# Launch_Shield.net
KiCad netlist of a schematic drawn in EAGLE
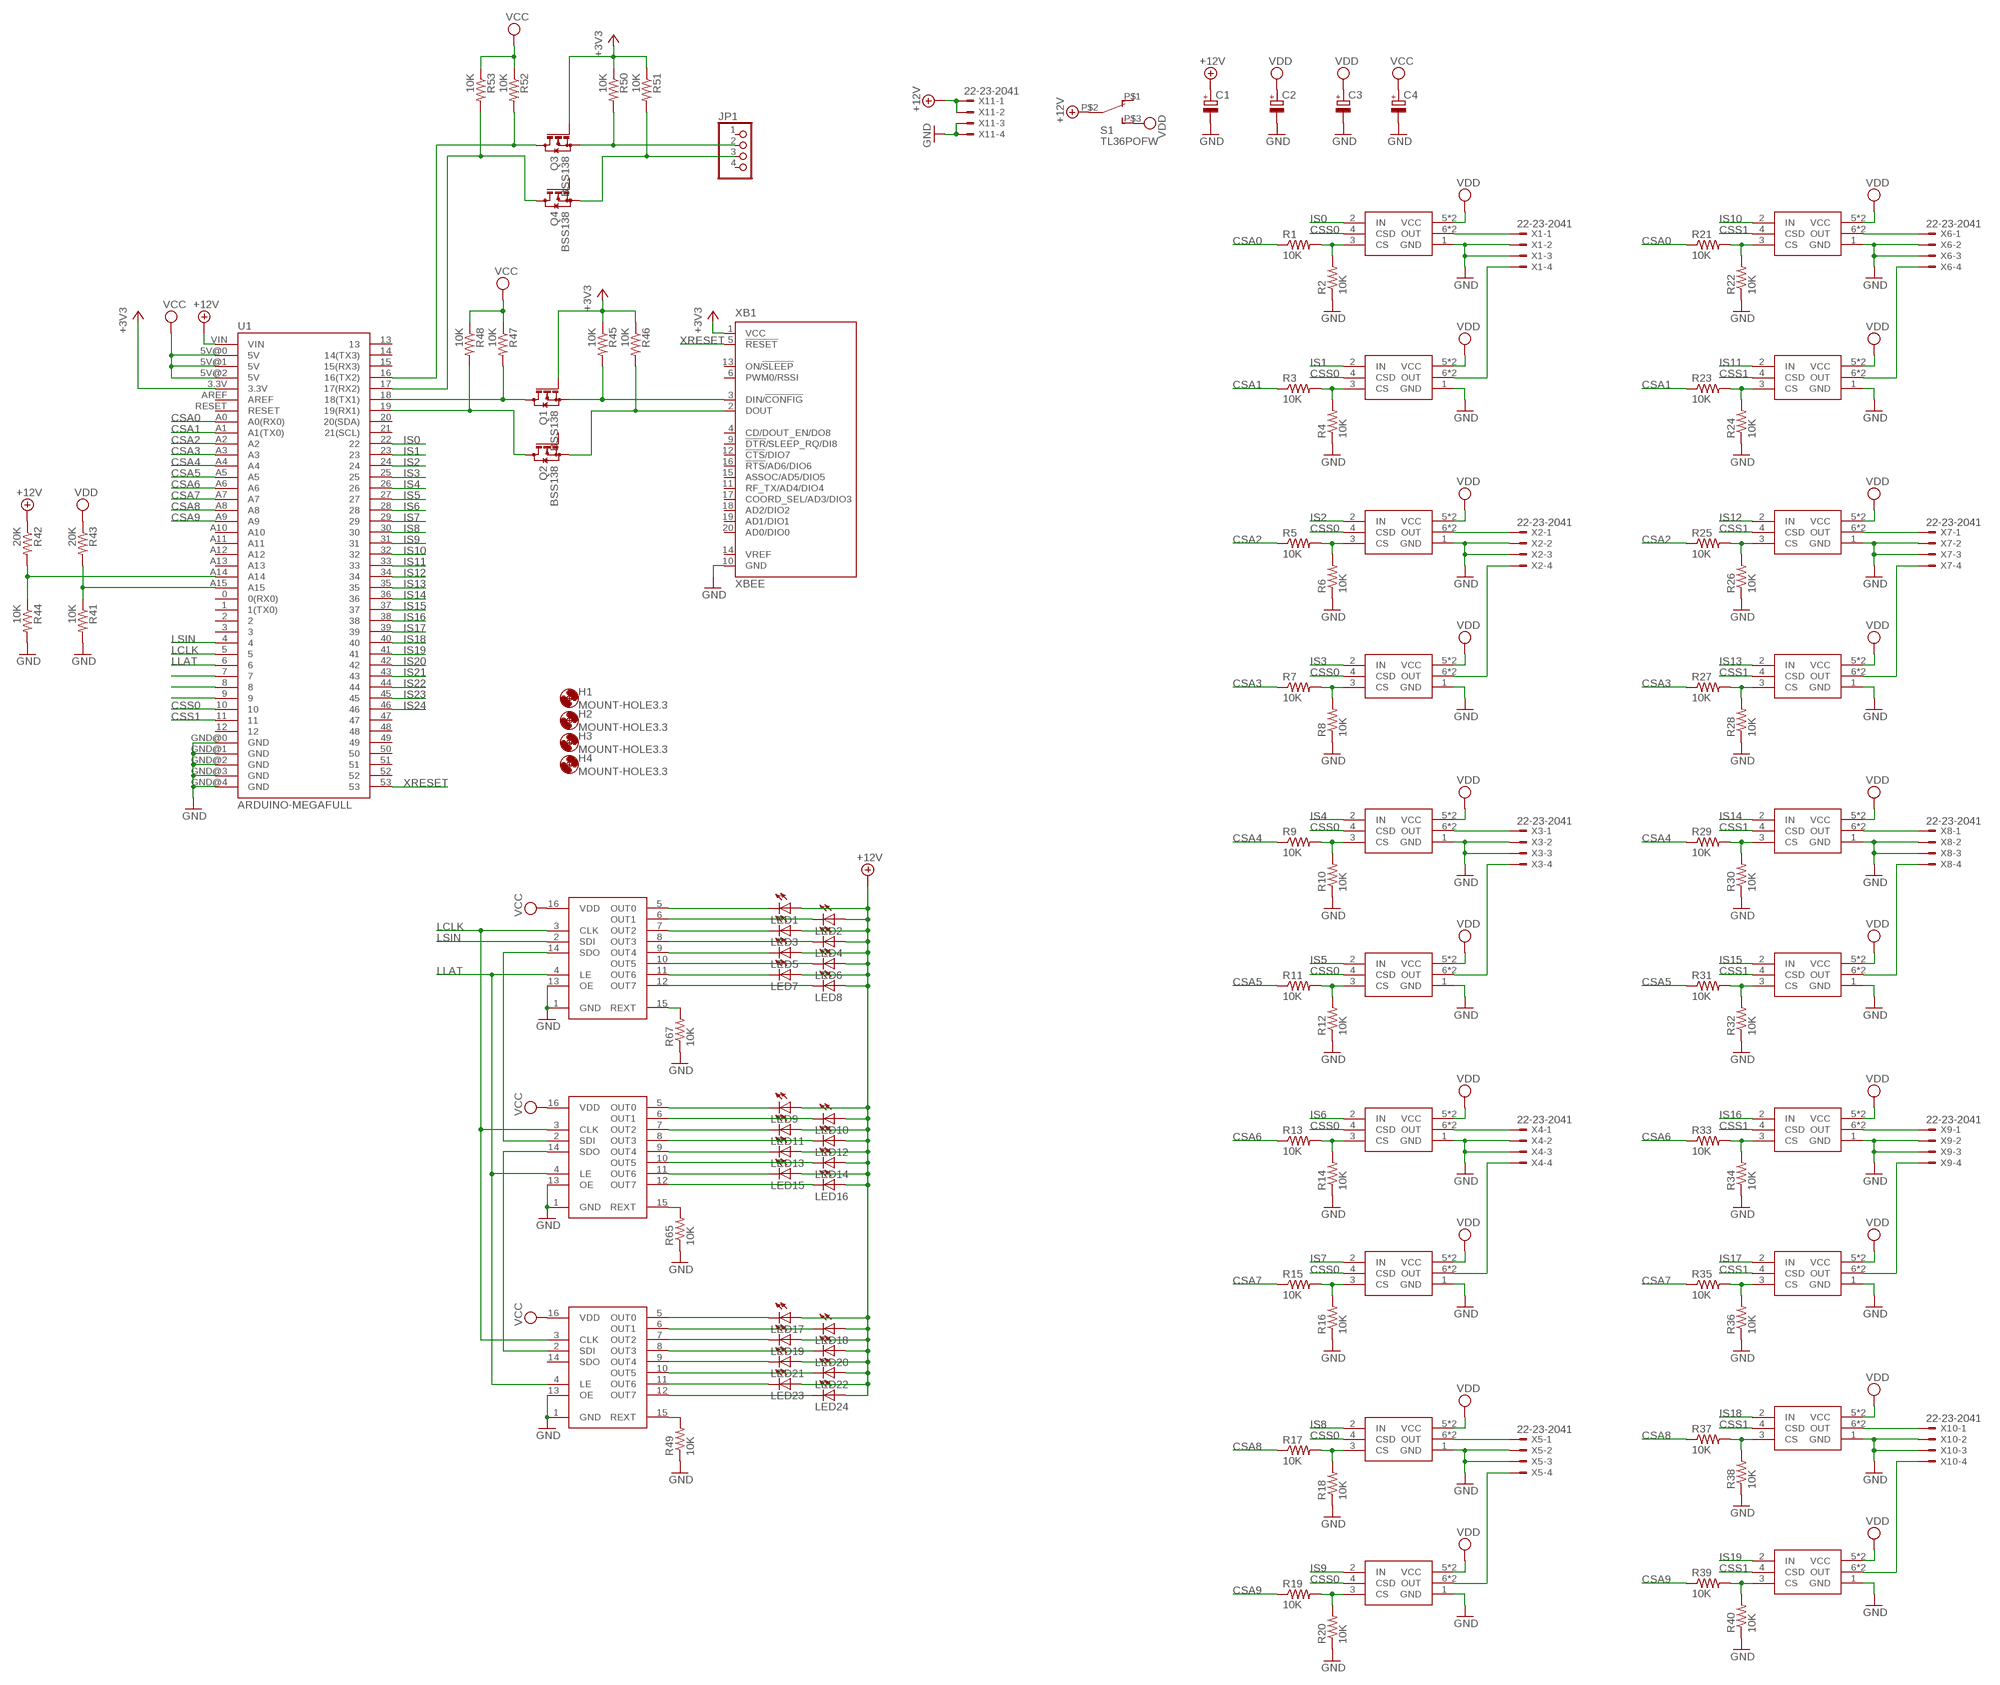
[diagram p0: schematic, sheet 1]

(export (version "E")
  (design (tool "Eeschema 10.0.6"))
  (components
    (comp (ref "C1")
      (value "CPOL-EUE5-6")
      (footprint "eagle-import:E5-6")
      (libsource (lib "eagle-import") (part "CPOL-EUE5-6"))
    )
    (comp (ref "C2")
      (value "CPOL-EUE5-6")
      (footprint "eagle-import:E5-6")
      (libsource (lib "eagle-import") (part "CPOL-EUE5-6"))
    )
    (comp (ref "C3")
      (value "CPOL-EUE5-6")
      (footprint "eagle-import:E5-6")
      (libsource (lib "eagle-import") (part "CPOL-EUE5-6"))
    )
    (comp (ref "C4")
      (value "CPOL-EUE5-6")
      (footprint "eagle-import:E5-6")
      (libsource (lib "eagle-import") (part "CPOL-EUE5-6"))
    )
    (comp (ref "H1")
      (value "MOUNT-HOLE3.3")
      (footprint "eagle-import:3,3")
      (libsource (lib "eagle-import") (part "MOUNT-HOLE3.3"))
    )
    (comp (ref "H2")
      (value "MOUNT-HOLE3.3")
      (footprint "eagle-import:3,3")
      (libsource (lib "eagle-import") (part "MOUNT-HOLE3.3"))
    )
    (comp (ref "H3")
      (value "MOUNT-HOLE3.3")
      (footprint "eagle-import:3,3")
      (libsource (lib "eagle-import") (part "MOUNT-HOLE3.3"))
    )
    (comp (ref "H4")
      (value "MOUNT-HOLE3.3")
      (footprint "eagle-import:3,3")
      (libsource (lib "eagle-import") (part "MOUNT-HOLE3.3"))
    )
    (comp (ref "JP1")
      (value "PINHD-1X4")
      (footprint "eagle-import:1X04")
      (libsource (lib "eagle-import") (part "PINHD-1X4"))
    )
    (comp (ref "LED1")
      (value "LEDCHIPLED_0805")
      (footprint "eagle-import:CHIPLED_0805")
      (libsource (lib "eagle-import") (part "LEDCHIPLED_0805"))
    )
    (comp (ref "LED2")
      (value "LEDCHIPLED_0805")
      (footprint "eagle-import:CHIPLED_0805")
      (libsource (lib "eagle-import") (part "LEDCHIPLED_0805"))
    )
    (comp (ref "LED3")
      (value "LEDCHIPLED_0805")
      (footprint "eagle-import:CHIPLED_0805")
      (libsource (lib "eagle-import") (part "LEDCHIPLED_0805"))
    )
    (comp (ref "LED4")
      (value "LEDCHIPLED_0805")
      (footprint "eagle-import:CHIPLED_0805")
      (libsource (lib "eagle-import") (part "LEDCHIPLED_0805"))
    )
    (comp (ref "LED5")
      (value "LEDCHIPLED_0805")
      (footprint "eagle-import:CHIPLED_0805")
      (libsource (lib "eagle-import") (part "LEDCHIPLED_0805"))
    )
    (comp (ref "LED6")
      (value "LEDCHIPLED_0805")
      (footprint "eagle-import:CHIPLED_0805")
      (libsource (lib "eagle-import") (part "LEDCHIPLED_0805"))
    )
    (comp (ref "LED7")
      (value "LEDCHIPLED_0805")
      (footprint "eagle-import:CHIPLED_0805")
      (libsource (lib "eagle-import") (part "LEDCHIPLED_0805"))
    )
    (comp (ref "LED8")
      (value "LEDCHIPLED_0805")
      (footprint "eagle-import:CHIPLED_0805")
      (libsource (lib "eagle-import") (part "LEDCHIPLED_0805"))
    )
    (comp (ref "LED9")
      (value "LEDCHIPLED_0805")
      (footprint "eagle-import:CHIPLED_0805")
      (libsource (lib "eagle-import") (part "LEDCHIPLED_0805"))
    )
    (comp (ref "LED10")
      (value "LEDCHIPLED_0805")
      (footprint "eagle-import:CHIPLED_0805")
      (libsource (lib "eagle-import") (part "LEDCHIPLED_0805"))
    )
    (comp (ref "LED11")
      (value "LEDCHIPLED_0805")
      (footprint "eagle-import:CHIPLED_0805")
      (libsource (lib "eagle-import") (part "LEDCHIPLED_0805"))
    )
    (comp (ref "LED12")
      (value "LEDCHIPLED_0805")
      (footprint "eagle-import:CHIPLED_0805")
      (libsource (lib "eagle-import") (part "LEDCHIPLED_0805"))
    )
    (comp (ref "LED13")
      (value "LEDCHIPLED_0805")
      (footprint "eagle-import:CHIPLED_0805")
      (libsource (lib "eagle-import") (part "LEDCHIPLED_0805"))
    )
    (comp (ref "LED14")
      (value "LEDCHIPLED_0805")
      (footprint "eagle-import:CHIPLED_0805")
      (libsource (lib "eagle-import") (part "LEDCHIPLED_0805"))
    )
    (comp (ref "LED15")
      (value "LEDCHIPLED_0805")
      (footprint "eagle-import:CHIPLED_0805")
      (libsource (lib "eagle-import") (part "LEDCHIPLED_0805"))
    )
    (comp (ref "LED16")
      (value "LEDCHIPLED_0805")
      (footprint "eagle-import:CHIPLED_0805")
      (libsource (lib "eagle-import") (part "LEDCHIPLED_0805"))
    )
    (comp (ref "LED17")
      (value "LEDCHIPLED_0805")
      (footprint "eagle-import:CHIPLED_0805")
      (libsource (lib "eagle-import") (part "LEDCHIPLED_0805"))
    )
    (comp (ref "LED18")
      (value "LEDCHIPLED_0805")
      (footprint "eagle-import:CHIPLED_0805")
      (libsource (lib "eagle-import") (part "LEDCHIPLED_0805"))
    )
    (comp (ref "LED19")
      (value "LEDCHIPLED_0805")
      (footprint "eagle-import:CHIPLED_0805")
      (libsource (lib "eagle-import") (part "LEDCHIPLED_0805"))
    )
    (comp (ref "LED20")
      (value "LEDCHIPLED_0805")
      (footprint "eagle-import:CHIPLED_0805")
      (libsource (lib "eagle-import") (part "LEDCHIPLED_0805"))
    )
    (comp (ref "LED21")
      (value "LEDCHIPLED_0805")
      (footprint "eagle-import:CHIPLED_0805")
      (libsource (lib "eagle-import") (part "LEDCHIPLED_0805"))
    )
    (comp (ref "LED22")
      (value "LEDCHIPLED_0805")
      (footprint "eagle-import:CHIPLED_0805")
      (libsource (lib "eagle-import") (part "LEDCHIPLED_0805"))
    )
    (comp (ref "LED23")
      (value "LEDCHIPLED_0805")
      (footprint "eagle-import:CHIPLED_0805")
      (libsource (lib "eagle-import") (part "LEDCHIPLED_0805"))
    )
    (comp (ref "LED24")
      (value "LEDCHIPLED_0805")
      (footprint "eagle-import:CHIPLED_0805")
      (libsource (lib "eagle-import") (part "LEDCHIPLED_0805"))
    )
    (comp (ref "Q1")
      (value "BSS138")
      (footprint "eagle-import:SOT23")
      (libsource (lib "eagle-import") (part "BSS123"))
    )
    (comp (ref "Q2")
      (value "BSS138")
      (footprint "eagle-import:SOT23")
      (libsource (lib "eagle-import") (part "BSS123"))
    )
    (comp (ref "Q3")
      (value "BSS138")
      (footprint "eagle-import:SOT23")
      (libsource (lib "eagle-import") (part "BSS123"))
    )
    (comp (ref "Q4")
      (value "BSS138")
      (footprint "eagle-import:SOT23")
      (libsource (lib "eagle-import") (part "BSS123"))
    )
    (comp (ref "R1")
      (value "10K")
      (footprint "eagle-import:R0603")
      (libsource (lib "eagle-import") (part "R-US_R0603"))
    )
    (comp (ref "R2")
      (value "10K")
      (footprint "eagle-import:R0603")
      (libsource (lib "eagle-import") (part "R-US_R0603"))
    )
    (comp (ref "R3")
      (value "10K")
      (footprint "eagle-import:R0603")
      (libsource (lib "eagle-import") (part "R-US_R0603"))
    )
    (comp (ref "R4")
      (value "10K")
      (footprint "eagle-import:R0603")
      (libsource (lib "eagle-import") (part "R-US_R0603"))
    )
    (comp (ref "R5")
      (value "10K")
      (footprint "eagle-import:R0603")
      (libsource (lib "eagle-import") (part "R-US_R0603"))
    )
    (comp (ref "R6")
      (value "10K")
      (footprint "eagle-import:R0603")
      (libsource (lib "eagle-import") (part "R-US_R0603"))
    )
    (comp (ref "R7")
      (value "10K")
      (footprint "eagle-import:R0603")
      (libsource (lib "eagle-import") (part "R-US_R0603"))
    )
    (comp (ref "R8")
      (value "10K")
      (footprint "eagle-import:R0603")
      (libsource (lib "eagle-import") (part "R-US_R0603"))
    )
    (comp (ref "R9")
      (value "10K")
      (footprint "eagle-import:R0603")
      (libsource (lib "eagle-import") (part "R-US_R0603"))
    )
    (comp (ref "R10")
      (value "10K")
      (footprint "eagle-import:R0603")
      (libsource (lib "eagle-import") (part "R-US_R0603"))
    )
    (comp (ref "R11")
      (value "10K")
      (footprint "eagle-import:R0603")
      (libsource (lib "eagle-import") (part "R-US_R0603"))
    )
    (comp (ref "R12")
      (value "10K")
      (footprint "eagle-import:R0603")
      (libsource (lib "eagle-import") (part "R-US_R0603"))
    )
    (comp (ref "R13")
      (value "10K")
      (footprint "eagle-import:R0603")
      (libsource (lib "eagle-import") (part "R-US_R0603"))
    )
    (comp (ref "R14")
      (value "10K")
      (footprint "eagle-import:R0603")
      (libsource (lib "eagle-import") (part "R-US_R0603"))
    )
    (comp (ref "R15")
      (value "10K")
      (footprint "eagle-import:R0603")
      (libsource (lib "eagle-import") (part "R-US_R0603"))
    )
    (comp (ref "R16")
      (value "10K")
      (footprint "eagle-import:R0603")
      (libsource (lib "eagle-import") (part "R-US_R0603"))
    )
    (comp (ref "R17")
      (value "10K")
      (footprint "eagle-import:R0603")
      (libsource (lib "eagle-import") (part "R-US_R0603"))
    )
    (comp (ref "R18")
      (value "10K")
      (footprint "eagle-import:R0603")
      (libsource (lib "eagle-import") (part "R-US_R0603"))
    )
    (comp (ref "R19")
      (value "10K")
      (footprint "eagle-import:R0603")
      (libsource (lib "eagle-import") (part "R-US_R0603"))
    )
    (comp (ref "R20")
      (value "10K")
      (footprint "eagle-import:R0603")
      (libsource (lib "eagle-import") (part "R-US_R0603"))
    )
    (comp (ref "R21")
      (value "10K")
      (footprint "eagle-import:R0603")
      (libsource (lib "eagle-import") (part "R-US_R0603"))
    )
    (comp (ref "R22")
      (value "10K")
      (footprint "eagle-import:R0603")
      (libsource (lib "eagle-import") (part "R-US_R0603"))
    )
    (comp (ref "R23")
      (value "10K")
      (footprint "eagle-import:R0603")
      (libsource (lib "eagle-import") (part "R-US_R0603"))
    )
    (comp (ref "R24")
      (value "10K")
      (footprint "eagle-import:R0603")
      (libsource (lib "eagle-import") (part "R-US_R0603"))
    )
    (comp (ref "R25")
      (value "10K")
      (footprint "eagle-import:R0603")
      (libsource (lib "eagle-import") (part "R-US_R0603"))
    )
    (comp (ref "R26")
      (value "10K")
      (footprint "eagle-import:R0603")
      (libsource (lib "eagle-import") (part "R-US_R0603"))
    )
    (comp (ref "R27")
      (value "10K")
      (footprint "eagle-import:R0603")
      (libsource (lib "eagle-import") (part "R-US_R0603"))
    )
    (comp (ref "R28")
      (value "10K")
      (footprint "eagle-import:R0603")
      (libsource (lib "eagle-import") (part "R-US_R0603"))
    )
    (comp (ref "R29")
      (value "10K")
      (footprint "eagle-import:R0603")
      (libsource (lib "eagle-import") (part "R-US_R0603"))
    )
    (comp (ref "R30")
      (value "10K")
      (footprint "eagle-import:R0603")
      (libsource (lib "eagle-import") (part "R-US_R0603"))
    )
    (comp (ref "R31")
      (value "10K")
      (footprint "eagle-import:R0603")
      (libsource (lib "eagle-import") (part "R-US_R0603"))
    )
    (comp (ref "R32")
      (value "10K")
      (footprint "eagle-import:R0603")
      (libsource (lib "eagle-import") (part "R-US_R0603"))
    )
    (comp (ref "R33")
      (value "10K")
      (footprint "eagle-import:R0603")
      (libsource (lib "eagle-import") (part "R-US_R0603"))
    )
    (comp (ref "R34")
      (value "10K")
      (footprint "eagle-import:R0603")
      (libsource (lib "eagle-import") (part "R-US_R0603"))
    )
    (comp (ref "R35")
      (value "10K")
      (footprint "eagle-import:R0603")
      (libsource (lib "eagle-import") (part "R-US_R0603"))
    )
    (comp (ref "R36")
      (value "10K")
      (footprint "eagle-import:R0603")
      (libsource (lib "eagle-import") (part "R-US_R0603"))
    )
    (comp (ref "R37")
      (value "10K")
      (footprint "eagle-import:R0603")
      (libsource (lib "eagle-import") (part "R-US_R0603"))
    )
    (comp (ref "R38")
      (value "10K")
      (footprint "eagle-import:R0603")
      (libsource (lib "eagle-import") (part "R-US_R0603"))
    )
    (comp (ref "R39")
      (value "10K")
      (footprint "eagle-import:R0603")
      (libsource (lib "eagle-import") (part "R-US_R0603"))
    )
    (comp (ref "R40")
      (value "10K")
      (footprint "eagle-import:R0603")
      (libsource (lib "eagle-import") (part "R-US_R0603"))
    )
    (comp (ref "R41")
      (value "10K")
      (footprint "eagle-import:R0603")
      (libsource (lib "eagle-import") (part "R-US_R0603"))
    )
    (comp (ref "R42")
      (value "20K")
      (footprint "eagle-import:R0603")
      (libsource (lib "eagle-import") (part "R-US_R0603"))
    )
    (comp (ref "R43")
      (value "20K")
      (footprint "eagle-import:R0603")
      (libsource (lib "eagle-import") (part "R-US_R0603"))
    )
    (comp (ref "R44")
      (value "10K")
      (footprint "eagle-import:R0603")
      (libsource (lib "eagle-import") (part "R-US_R0603"))
    )
    (comp (ref "R45")
      (value "10K")
      (footprint "eagle-import:R0603")
      (libsource (lib "eagle-import") (part "R-US_R0603"))
    )
    (comp (ref "R46")
      (value "10K")
      (footprint "eagle-import:R0603")
      (libsource (lib "eagle-import") (part "R-US_R0603"))
    )
    (comp (ref "R47")
      (value "10K")
      (footprint "eagle-import:R0603")
      (libsource (lib "eagle-import") (part "R-US_R0603"))
    )
    (comp (ref "R48")
      (value "10K")
      (footprint "eagle-import:R0603")
      (libsource (lib "eagle-import") (part "R-US_R0603"))
    )
    (comp (ref "R49")
      (value "10K")
      (footprint "eagle-import:R0603")
      (libsource (lib "eagle-import") (part "R-US_R0603"))
    )
    (comp (ref "R50")
      (value "10K")
      (footprint "eagle-import:R0603")
      (libsource (lib "eagle-import") (part "R-US_R0603"))
    )
    (comp (ref "R51")
      (value "10K")
      (footprint "eagle-import:R0603")
      (libsource (lib "eagle-import") (part "R-US_R0603"))
    )
    (comp (ref "R52")
      (value "10K")
      (footprint "eagle-import:R0603")
      (libsource (lib "eagle-import") (part "R-US_R0603"))
    )
    (comp (ref "R53")
      (value "10K")
      (footprint "eagle-import:R0603")
      (libsource (lib "eagle-import") (part "R-US_R0603"))
    )
    (comp (ref "R65")
      (value "10K")
      (footprint "eagle-import:R0603")
      (libsource (lib "eagle-import") (part "R-US_R0603"))
    )
    (comp (ref "R67")
      (value "10K")
      (footprint "eagle-import:R0603")
      (libsource (lib "eagle-import") (part "R-US_R0603"))
    )
    (comp (ref "S1")
      (value "TL36POFW")
      (footprint "eagle-import:TOGGLE")
      (libsource (lib "eagle-import") (part "TL36POFW"))
    )
    (comp (ref "U$1")
      (value "VN5E160MS-E")
      (footprint "eagle-import:SOIC8")
      (libsource (lib "eagle-import") (part "VN5E160MS-E"))
    )
    (comp (ref "U$2")
      (value "VN5E160MS-E")
      (footprint "eagle-import:SOIC8")
      (libsource (lib "eagle-import") (part "VN5E160MS-E"))
    )
    (comp (ref "U$3")
      (value "VN5E160MS-E")
      (footprint "eagle-import:SOIC8")
      (libsource (lib "eagle-import") (part "VN5E160MS-E"))
    )
    (comp (ref "U$4")
      (value "VN5E160MS-E")
      (footprint "eagle-import:SOIC8")
      (libsource (lib "eagle-import") (part "VN5E160MS-E"))
    )
    (comp (ref "U$5")
      (value "VN5E160MS-E")
      (footprint "eagle-import:SOIC8")
      (libsource (lib "eagle-import") (part "VN5E160MS-E"))
    )
    (comp (ref "U$6")
      (value "VN5E160MS-E")
      (footprint "eagle-import:SOIC8")
      (libsource (lib "eagle-import") (part "VN5E160MS-E"))
    )
    (comp (ref "U$7")
      (value "VN5E160MS-E")
      (footprint "eagle-import:SOIC8")
      (libsource (lib "eagle-import") (part "VN5E160MS-E"))
    )
    (comp (ref "U$8")
      (value "VN5E160MS-E")
      (footprint "eagle-import:SOIC8")
      (libsource (lib "eagle-import") (part "VN5E160MS-E"))
    )
    (comp (ref "U$9")
      (value "VN5E160MS-E")
      (footprint "eagle-import:SOIC8")
      (libsource (lib "eagle-import") (part "VN5E160MS-E"))
    )
    (comp (ref "U$10")
      (value "VN5E160MS-E")
      (footprint "eagle-import:SOIC8")
      (libsource (lib "eagle-import") (part "VN5E160MS-E"))
    )
    (comp (ref "U$11")
      (value "VN5E160MS-E")
      (footprint "eagle-import:SOIC8")
      (libsource (lib "eagle-import") (part "VN5E160MS-E"))
    )
    (comp (ref "U$12")
      (value "VN5E160MS-E")
      (footprint "eagle-import:SOIC8")
      (libsource (lib "eagle-import") (part "VN5E160MS-E"))
    )
    (comp (ref "U$13")
      (value "VN5E160MS-E")
      (footprint "eagle-import:SOIC8")
      (libsource (lib "eagle-import") (part "VN5E160MS-E"))
    )
    (comp (ref "U$14")
      (value "VN5E160MS-E")
      (footprint "eagle-import:SOIC8")
      (libsource (lib "eagle-import") (part "VN5E160MS-E"))
    )
    (comp (ref "U$15")
      (value "VN5E160MS-E")
      (footprint "eagle-import:SOIC8")
      (libsource (lib "eagle-import") (part "VN5E160MS-E"))
    )
    (comp (ref "U$16")
      (value "VN5E160MS-E")
      (footprint "eagle-import:SOIC8")
      (libsource (lib "eagle-import") (part "VN5E160MS-E"))
    )
    (comp (ref "U$17")
      (value "VN5E160MS-E")
      (footprint "eagle-import:SOIC8")
      (libsource (lib "eagle-import") (part "VN5E160MS-E"))
    )
    (comp (ref "U$18")
      (value "VN5E160MS-E")
      (footprint "eagle-import:SOIC8")
      (libsource (lib "eagle-import") (part "VN5E160MS-E"))
    )
    (comp (ref "U$19")
      (value "VN5E160MS-E")
      (footprint "eagle-import:SOIC8")
      (libsource (lib "eagle-import") (part "VN5E160MS-E"))
    )
    (comp (ref "U$20")
      (value "VN5E160MS-E")
      (footprint "eagle-import:SOIC8")
      (libsource (lib "eagle-import") (part "VN5E160MS-E"))
    )
    (comp (ref "U$21")
      (value "TLC5916")
      (footprint "eagle-import:D_R-PDSO-G16")
      (libsource (lib "eagle-import") (part "TLC5916"))
    )
    (comp (ref "U$22")
      (value "TLC5916")
      (footprint "eagle-import:D_R-PDSO-G16")
      (libsource (lib "eagle-import") (part "TLC5916"))
    )
    (comp (ref "U$23")
      (value "TLC5916")
      (footprint "eagle-import:D_R-PDSO-G16")
      (libsource (lib "eagle-import") (part "TLC5916"))
    )
    (comp (ref "U1")
      (value "ARDUINO-MEGAFULL")
      (footprint "eagle-import:ARDUINO_MEGA")
      (libsource (lib "eagle-import") (part "ARDUINO-MEGAFULL"))
    )
    (comp (ref "X1")
      (value "22-23-2041")
      (footprint "eagle-import:22-23-2041")
      (fields (field (name "MF") "MOLEX"))
      (libsource (lib "eagle-import") (part "22-23-2041"))
    )
    (comp (ref "X2")
      (value "22-23-2041")
      (footprint "eagle-import:22-23-2041")
      (fields (field (name "MF") "MOLEX"))
      (libsource (lib "eagle-import") (part "22-23-2041"))
    )
    (comp (ref "X3")
      (value "22-23-2041")
      (footprint "eagle-import:22-23-2041")
      (fields (field (name "MF") "MOLEX"))
      (libsource (lib "eagle-import") (part "22-23-2041"))
    )
    (comp (ref "X4")
      (value "22-23-2041")
      (footprint "eagle-import:22-23-2041")
      (fields (field (name "MF") "MOLEX"))
      (libsource (lib "eagle-import") (part "22-23-2041"))
    )
    (comp (ref "X5")
      (value "22-23-2041")
      (footprint "eagle-import:22-23-2041")
      (fields (field (name "MF") "MOLEX"))
      (libsource (lib "eagle-import") (part "22-23-2041"))
    )
    (comp (ref "X6")
      (value "22-23-2041")
      (footprint "eagle-import:22-23-2041")
      (fields (field (name "MF") "MOLEX"))
      (libsource (lib "eagle-import") (part "22-23-2041"))
    )
    (comp (ref "X7")
      (value "22-23-2041")
      (footprint "eagle-import:22-23-2041")
      (fields (field (name "MF") "MOLEX"))
      (libsource (lib "eagle-import") (part "22-23-2041"))
    )
    (comp (ref "X8")
      (value "22-23-2041")
      (footprint "eagle-import:22-23-2041")
      (fields (field (name "MF") "MOLEX"))
      (libsource (lib "eagle-import") (part "22-23-2041"))
    )
    (comp (ref "X9")
      (value "22-23-2041")
      (footprint "eagle-import:22-23-2041")
      (fields (field (name "MF") "MOLEX"))
      (libsource (lib "eagle-import") (part "22-23-2041"))
    )
    (comp (ref "X10")
      (value "22-23-2041")
      (footprint "eagle-import:22-23-2041")
      (fields (field (name "MF") "MOLEX"))
      (libsource (lib "eagle-import") (part "22-23-2041"))
    )
    (comp (ref "X11")
      (value "22-23-2041")
      (footprint "eagle-import:22-23-2041")
      (fields (field (name "MF") "MOLEX"))
      (libsource (lib "eagle-import") (part "22-23-2041"))
    )
    (comp (ref "XB1")
      (value "XBEE")
      (footprint "eagle-import:XBEE")
      (fields (field (name "MPN") "XBP24-Z7UIT-004"))
      (libsource (lib "eagle-import") (part "XBEE"))
    )
  )
  (nets
    (net (code "1") (name "+3V3") (class "Default")
      (node (ref "Q1") (pin "1") (pinfunction "G_1") (pintype "passive"))
      (node (ref "Q3") (pin "1") (pinfunction "G_1") (pintype "passive"))
      (node (ref "R45") (pin "1") (pinfunction "1_1") (pintype "passive"))
      (node (ref "R46") (pin "1") (pinfunction "1_1") (pintype "passive"))
      (node (ref "R50") (pin "1") (pinfunction "1_1") (pintype "passive"))
      (node (ref "R51") (pin "1") (pinfunction "1_1") (pintype "passive"))
      (node (ref "U1") (pin "3.3V") (pinfunction "3.3V_3.3V") (pintype "bidirectional"))
      (node (ref "XB1") (pin "1") (pinfunction "VCC_1") (pintype "power_in"))
    )
    (net (code "2") (name "+12V") (class "Default")
      (node (ref "C1") (pin "+") (pinfunction "+_+") (pintype "passive"))
      (node (ref "LED1") (pin "A") (pinfunction "A_A") (pintype "passive"))
      (node (ref "LED10") (pin "A") (pinfunction "A_A") (pintype "passive"))
      (node (ref "LED11") (pin "A") (pinfunction "A_A") (pintype "passive"))
      (node (ref "LED12") (pin "A") (pinfunction "A_A") (pintype "passive"))
      (node (ref "LED13") (pin "A") (pinfunction "A_A") (pintype "passive"))
      (node (ref "LED14") (pin "A") (pinfunction "A_A") (pintype "passive"))
      (node (ref "LED15") (pin "A") (pinfunction "A_A") (pintype "passive"))
      (node (ref "LED16") (pin "A") (pinfunction "A_A") (pintype "passive"))
      (node (ref "LED17") (pin "A") (pinfunction "A_A") (pintype "passive"))
      (node (ref "LED18") (pin "A") (pinfunction "A_A") (pintype "passive"))
      (node (ref "LED19") (pin "A") (pinfunction "A_A") (pintype "passive"))
      (node (ref "LED2") (pin "A") (pinfunction "A_A") (pintype "passive"))
      (node (ref "LED20") (pin "A") (pinfunction "A_A") (pintype "passive"))
      (node (ref "LED21") (pin "A") (pinfunction "A_A") (pintype "passive"))
      (node (ref "LED22") (pin "A") (pinfunction "A_A") (pintype "passive"))
      (node (ref "LED23") (pin "A") (pinfunction "A_A") (pintype "passive"))
      (node (ref "LED24") (pin "A") (pinfunction "A_A") (pintype "passive"))
      (node (ref "LED3") (pin "A") (pinfunction "A_A") (pintype "passive"))
      (node (ref "LED4") (pin "A") (pinfunction "A_A") (pintype "passive"))
      (node (ref "LED5") (pin "A") (pinfunction "A_A") (pintype "passive"))
      (node (ref "LED6") (pin "A") (pinfunction "A_A") (pintype "passive"))
      (node (ref "LED7") (pin "A") (pinfunction "A_A") (pintype "passive"))
      (node (ref "LED8") (pin "A") (pinfunction "A_A") (pintype "passive"))
      (node (ref "LED9") (pin "A") (pinfunction "A_A") (pintype "passive"))
      (node (ref "R42") (pin "1") (pinfunction "1_1") (pintype "passive"))
      (node (ref "S1") (pin "P$2") (pinfunction "P_P$2") (pintype "passive"))
      (node (ref "U1") (pin "VIN") (pinfunction "VIN_VIN") (pintype "bidirectional"))
      (node (ref "X11") (pin "1") (pinfunction "S_1") (pintype "passive"))
      (node (ref "X11") (pin "2") (pinfunction "S_2") (pintype "passive"))
    )
    (net (code "3") (name "/CSA0") (class "Default")
      (node (ref "R1") (pin "1") (pinfunction "1_1") (pintype "passive"))
      (node (ref "R21") (pin "1") (pinfunction "1_1") (pintype "passive"))
      (node (ref "U1") (pin "A0") (pinfunction "A0(RX0)_A0") (pintype "bidirectional"))
    )
    (net (code "4") (name "/CSA1") (class "Default")
      (node (ref "R23") (pin "1") (pinfunction "1_1") (pintype "passive"))
      (node (ref "R3") (pin "1") (pinfunction "1_1") (pintype "passive"))
      (node (ref "U1") (pin "A1") (pinfunction "A1(TX0)_A1") (pintype "bidirectional"))
    )
    (net (code "5") (name "/CSA2") (class "Default")
      (node (ref "R25") (pin "1") (pinfunction "1_1") (pintype "passive"))
      (node (ref "R5") (pin "1") (pinfunction "1_1") (pintype "passive"))
      (node (ref "U1") (pin "A2") (pinfunction "A2_A2") (pintype "bidirectional"))
    )
    (net (code "6") (name "/CSA3") (class "Default")
      (node (ref "R27") (pin "1") (pinfunction "1_1") (pintype "passive"))
      (node (ref "R7") (pin "1") (pinfunction "1_1") (pintype "passive"))
      (node (ref "U1") (pin "A3") (pinfunction "A3_A3") (pintype "bidirectional"))
    )
    (net (code "7") (name "/CSA4") (class "Default")
      (node (ref "R29") (pin "1") (pinfunction "1_1") (pintype "passive"))
      (node (ref "R9") (pin "1") (pinfunction "1_1") (pintype "passive"))
      (node (ref "U1") (pin "A4") (pinfunction "A4_A4") (pintype "bidirectional"))
    )
    (net (code "8") (name "/CSA5") (class "Default")
      (node (ref "R11") (pin "1") (pinfunction "1_1") (pintype "passive"))
      (node (ref "R31") (pin "1") (pinfunction "1_1") (pintype "passive"))
      (node (ref "U1") (pin "A5") (pinfunction "A5_A5") (pintype "bidirectional"))
    )
    (net (code "9") (name "/CSA6") (class "Default")
      (node (ref "R13") (pin "1") (pinfunction "1_1") (pintype "passive"))
      (node (ref "R33") (pin "1") (pinfunction "1_1") (pintype "passive"))
      (node (ref "U1") (pin "A6") (pinfunction "A6_A6") (pintype "bidirectional"))
    )
    (net (code "10") (name "/CSA7") (class "Default")
      (node (ref "R15") (pin "1") (pinfunction "1_1") (pintype "passive"))
      (node (ref "R35") (pin "1") (pinfunction "1_1") (pintype "passive"))
      (node (ref "U1") (pin "A7") (pinfunction "A7_A7") (pintype "bidirectional"))
    )
    (net (code "11") (name "/CSA8") (class "Default")
      (node (ref "R17") (pin "1") (pinfunction "1_1") (pintype "passive"))
      (node (ref "R37") (pin "1") (pinfunction "1_1") (pintype "passive"))
      (node (ref "U1") (pin "A8") (pinfunction "A8_A8") (pintype "bidirectional"))
    )
    (net (code "12") (name "/CSA9") (class "Default")
      (node (ref "R19") (pin "1") (pinfunction "1_1") (pintype "passive"))
      (node (ref "R39") (pin "1") (pinfunction "1_1") (pintype "passive"))
      (node (ref "U1") (pin "A9") (pinfunction "A9_A9") (pintype "bidirectional"))
    )
    (net (code "13") (name "/CSS0") (class "Default")
      (node (ref "U$1") (pin "4") (pinfunction "CSD_4") (pintype "bidirectional"))
      (node (ref "U$10") (pin "4") (pinfunction "CSD_4") (pintype "bidirectional"))
      (node (ref "U$2") (pin "4") (pinfunction "CSD_4") (pintype "bidirectional"))
      (node (ref "U$3") (pin "4") (pinfunction "CSD_4") (pintype "bidirectional"))
      (node (ref "U$4") (pin "4") (pinfunction "CSD_4") (pintype "bidirectional"))
      (node (ref "U$5") (pin "4") (pinfunction "CSD_4") (pintype "bidirectional"))
      (node (ref "U$6") (pin "4") (pinfunction "CSD_4") (pintype "bidirectional"))
      (node (ref "U$7") (pin "4") (pinfunction "CSD_4") (pintype "bidirectional"))
      (node (ref "U$8") (pin "4") (pinfunction "CSD_4") (pintype "bidirectional"))
      (node (ref "U$9") (pin "4") (pinfunction "CSD_4") (pintype "bidirectional"))
      (node (ref "U1") (pin "10") (pinfunction "10_10") (pintype "bidirectional"))
    )
    (net (code "14") (name "/CSS1") (class "Default")
      (node (ref "U$11") (pin "4") (pinfunction "CSD_4") (pintype "bidirectional"))
      (node (ref "U$12") (pin "4") (pinfunction "CSD_4") (pintype "bidirectional"))
      (node (ref "U$13") (pin "4") (pinfunction "CSD_4") (pintype "bidirectional"))
      (node (ref "U$14") (pin "4") (pinfunction "CSD_4") (pintype "bidirectional"))
      (node (ref "U$15") (pin "4") (pinfunction "CSD_4") (pintype "bidirectional"))
      (node (ref "U$16") (pin "4") (pinfunction "CSD_4") (pintype "bidirectional"))
      (node (ref "U$17") (pin "4") (pinfunction "CSD_4") (pintype "bidirectional"))
      (node (ref "U$18") (pin "4") (pinfunction "CSD_4") (pintype "bidirectional"))
      (node (ref "U$19") (pin "4") (pinfunction "CSD_4") (pintype "bidirectional"))
      (node (ref "U$20") (pin "4") (pinfunction "CSD_4") (pintype "bidirectional"))
      (node (ref "U1") (pin "11") (pinfunction "11_11") (pintype "bidirectional"))
    )
    (net (code "15") (name "/IS0") (class "Default")
      (node (ref "U$1") (pin "2") (pinfunction "IN_2") (pintype "bidirectional"))
      (node (ref "U1") (pin "22") (pinfunction "22_22") (pintype "bidirectional"))
    )
    (net (code "16") (name "/IS1") (class "Default")
      (node (ref "U$2") (pin "2") (pinfunction "IN_2") (pintype "bidirectional"))
      (node (ref "U1") (pin "23") (pinfunction "23_23") (pintype "bidirectional"))
    )
    (net (code "17") (name "/IS2") (class "Default")
      (node (ref "U$3") (pin "2") (pinfunction "IN_2") (pintype "bidirectional"))
      (node (ref "U1") (pin "24") (pinfunction "24_24") (pintype "bidirectional"))
    )
    (net (code "18") (name "/IS3") (class "Default")
      (node (ref "U$4") (pin "2") (pinfunction "IN_2") (pintype "bidirectional"))
      (node (ref "U1") (pin "25") (pinfunction "25_25") (pintype "bidirectional"))
    )
    (net (code "19") (name "/IS4") (class "Default")
      (node (ref "U$5") (pin "2") (pinfunction "IN_2") (pintype "bidirectional"))
      (node (ref "U1") (pin "26") (pinfunction "26_26") (pintype "bidirectional"))
    )
    (net (code "20") (name "/IS5") (class "Default")
      (node (ref "U$6") (pin "2") (pinfunction "IN_2") (pintype "bidirectional"))
      (node (ref "U1") (pin "27") (pinfunction "27_27") (pintype "bidirectional"))
    )
    (net (code "21") (name "/IS6") (class "Default")
      (node (ref "U$7") (pin "2") (pinfunction "IN_2") (pintype "bidirectional"))
      (node (ref "U1") (pin "28") (pinfunction "28_28") (pintype "bidirectional"))
    )
    (net (code "22") (name "/IS7") (class "Default")
      (node (ref "U$8") (pin "2") (pinfunction "IN_2") (pintype "bidirectional"))
      (node (ref "U1") (pin "29") (pinfunction "29_29") (pintype "bidirectional"))
    )
    (net (code "23") (name "/IS8") (class "Default")
      (node (ref "U$9") (pin "2") (pinfunction "IN_2") (pintype "bidirectional"))
      (node (ref "U1") (pin "30") (pinfunction "30_30") (pintype "bidirectional"))
    )
    (net (code "24") (name "/IS9") (class "Default")
      (node (ref "U$10") (pin "2") (pinfunction "IN_2") (pintype "bidirectional"))
      (node (ref "U1") (pin "31") (pinfunction "31_31") (pintype "bidirectional"))
    )
    (net (code "25") (name "/IS10") (class "Default")
      (node (ref "U$11") (pin "2") (pinfunction "IN_2") (pintype "bidirectional"))
      (node (ref "U1") (pin "32") (pinfunction "32_32") (pintype "bidirectional"))
    )
    (net (code "26") (name "/IS11") (class "Default")
      (node (ref "U$12") (pin "2") (pinfunction "IN_2") (pintype "bidirectional"))
      (node (ref "U1") (pin "33") (pinfunction "33_33") (pintype "bidirectional"))
    )
    (net (code "27") (name "/IS12") (class "Default")
      (node (ref "U$13") (pin "2") (pinfunction "IN_2") (pintype "bidirectional"))
      (node (ref "U1") (pin "34") (pinfunction "34_34") (pintype "bidirectional"))
    )
    (net (code "28") (name "/IS13") (class "Default")
      (node (ref "U$14") (pin "2") (pinfunction "IN_2") (pintype "bidirectional"))
      (node (ref "U1") (pin "35") (pinfunction "35_35") (pintype "bidirectional"))
    )
    (net (code "29") (name "/IS14") (class "Default")
      (node (ref "U$15") (pin "2") (pinfunction "IN_2") (pintype "bidirectional"))
      (node (ref "U1") (pin "36") (pinfunction "36_36") (pintype "bidirectional"))
    )
    (net (code "30") (name "/IS15") (class "Default")
      (node (ref "U$16") (pin "2") (pinfunction "IN_2") (pintype "bidirectional"))
      (node (ref "U1") (pin "37") (pinfunction "37_37") (pintype "bidirectional"))
    )
    (net (code "31") (name "/IS16") (class "Default")
      (node (ref "U$17") (pin "2") (pinfunction "IN_2") (pintype "bidirectional"))
      (node (ref "U1") (pin "38") (pinfunction "38_38") (pintype "bidirectional"))
    )
    (net (code "32") (name "/IS17") (class "Default")
      (node (ref "U$18") (pin "2") (pinfunction "IN_2") (pintype "bidirectional"))
      (node (ref "U1") (pin "39") (pinfunction "39_39") (pintype "bidirectional"))
    )
    (net (code "33") (name "/IS18") (class "Default")
      (node (ref "U$19") (pin "2") (pinfunction "IN_2") (pintype "bidirectional"))
      (node (ref "U1") (pin "40") (pinfunction "40_40") (pintype "bidirectional"))
    )
    (net (code "34") (name "/IS19") (class "Default")
      (node (ref "U$20") (pin "2") (pinfunction "IN_2") (pintype "bidirectional"))
      (node (ref "U1") (pin "41") (pinfunction "41_41") (pintype "bidirectional"))
    )
    (net (code "35") (name "/IS20") (class "Default")
      (node (ref "U1") (pin "42") (pinfunction "42_42") (pintype "bidirectional"))
    )
    (net (code "36") (name "/IS21") (class "Default")
      (node (ref "U1") (pin "43") (pinfunction "43_43") (pintype "bidirectional"))
    )
    (net (code "37") (name "/IS22") (class "Default")
      (node (ref "U1") (pin "44") (pinfunction "44_44") (pintype "bidirectional"))
    )
    (net (code "38") (name "/IS23") (class "Default")
      (node (ref "U1") (pin "45") (pinfunction "45_45") (pintype "bidirectional"))
    )
    (net (code "39") (name "/IS24") (class "Default")
      (node (ref "U1") (pin "46") (pinfunction "46_46") (pintype "bidirectional"))
    )
    (net (code "40") (name "/LCLK") (class "Default")
      (node (ref "U$21") (pin "3") (pinfunction "CLK_3") (pintype "bidirectional"))
      (node (ref "U$22") (pin "3") (pinfunction "CLK_3") (pintype "bidirectional"))
      (node (ref "U$23") (pin "3") (pinfunction "CLK_3") (pintype "bidirectional"))
      (node (ref "U1") (pin "5") (pinfunction "5_5") (pintype "bidirectional"))
    )
    (net (code "41") (name "/LLAT") (class "Default")
      (node (ref "U$21") (pin "4") (pinfunction "LE_4") (pintype "bidirectional"))
      (node (ref "U$22") (pin "4") (pinfunction "LE_4") (pintype "bidirectional"))
      (node (ref "U$23") (pin "4") (pinfunction "LE_4") (pintype "bidirectional"))
      (node (ref "U1") (pin "6") (pinfunction "6_6") (pintype "bidirectional"))
    )
    (net (code "42") (name "/LSIN") (class "Default")
      (node (ref "U$21") (pin "2") (pinfunction "SDI_2") (pintype "bidirectional"))
      (node (ref "U1") (pin "4") (pinfunction "4_4") (pintype "bidirectional"))
    )
    (net (code "43") (name "/XRESET") (class "Default")
      (node (ref "U1") (pin "53") (pinfunction "53_53") (pintype "bidirectional"))
      (node (ref "XB1") (pin "5") (pinfunction "~{RESET}_5") (pintype "input"))
    )
    (net (code "44") (name "GND") (class "Default")
      (node (ref "C1") (pin "-") (pinfunction "-_-") (pintype "passive"))
      (node (ref "C2") (pin "-") (pinfunction "-_-") (pintype "passive"))
      (node (ref "C3") (pin "-") (pinfunction "-_-") (pintype "passive"))
      (node (ref "C4") (pin "-") (pinfunction "-_-") (pintype "passive"))
      (node (ref "R10") (pin "1") (pinfunction "1_1") (pintype "passive"))
      (node (ref "R12") (pin "1") (pinfunction "1_1") (pintype "passive"))
      (node (ref "R14") (pin "1") (pinfunction "1_1") (pintype "passive"))
      (node (ref "R16") (pin "1") (pinfunction "1_1") (pintype "passive"))
      (node (ref "R18") (pin "1") (pinfunction "1_1") (pintype "passive"))
      (node (ref "R2") (pin "1") (pinfunction "1_1") (pintype "passive"))
      (node (ref "R20") (pin "1") (pinfunction "1_1") (pintype "passive"))
      (node (ref "R22") (pin "1") (pinfunction "1_1") (pintype "passive"))
      (node (ref "R24") (pin "1") (pinfunction "1_1") (pintype "passive"))
      (node (ref "R26") (pin "1") (pinfunction "1_1") (pintype "passive"))
      (node (ref "R28") (pin "1") (pinfunction "1_1") (pintype "passive"))
      (node (ref "R30") (pin "1") (pinfunction "1_1") (pintype "passive"))
      (node (ref "R32") (pin "1") (pinfunction "1_1") (pintype "passive"))
      (node (ref "R34") (pin "1") (pinfunction "1_1") (pintype "passive"))
      (node (ref "R36") (pin "1") (pinfunction "1_1") (pintype "passive"))
      (node (ref "R38") (pin "1") (pinfunction "1_1") (pintype "passive"))
      (node (ref "R4") (pin "1") (pinfunction "1_1") (pintype "passive"))
      (node (ref "R40") (pin "1") (pinfunction "1_1") (pintype "passive"))
      (node (ref "R41") (pin "2") (pinfunction "2_2") (pintype "passive"))
      (node (ref "R44") (pin "2") (pinfunction "2_2") (pintype "passive"))
      (node (ref "R49") (pin "1") (pinfunction "1_1") (pintype "passive"))
      (node (ref "R6") (pin "1") (pinfunction "1_1") (pintype "passive"))
      (node (ref "R65") (pin "1") (pinfunction "1_1") (pintype "passive"))
      (node (ref "R67") (pin "1") (pinfunction "1_1") (pintype "passive"))
      (node (ref "R8") (pin "1") (pinfunction "1_1") (pintype "passive"))
      (node (ref "U$1") (pin "1") (pinfunction "GND_1") (pintype "power_in"))
      (node (ref "U$10") (pin "1") (pinfunction "GND_1") (pintype "power_in"))
      (node (ref "U$11") (pin "1") (pinfunction "GND_1") (pintype "power_in"))
      (node (ref "U$12") (pin "1") (pinfunction "GND_1") (pintype "power_in"))
      (node (ref "U$13") (pin "1") (pinfunction "GND_1") (pintype "power_in"))
      (node (ref "U$14") (pin "1") (pinfunction "GND_1") (pintype "power_in"))
      (node (ref "U$15") (pin "1") (pinfunction "GND_1") (pintype "power_in"))
      (node (ref "U$16") (pin "1") (pinfunction "GND_1") (pintype "power_in"))
      (node (ref "U$17") (pin "1") (pinfunction "GND_1") (pintype "power_in"))
      (node (ref "U$18") (pin "1") (pinfunction "GND_1") (pintype "power_in"))
      (node (ref "U$19") (pin "1") (pinfunction "GND_1") (pintype "power_in"))
      (node (ref "U$2") (pin "1") (pinfunction "GND_1") (pintype "power_in"))
      (node (ref "U$20") (pin "1") (pinfunction "GND_1") (pintype "power_in"))
      (node (ref "U$21") (pin "1") (pinfunction "GND_1") (pintype "bidirectional"))
      (node (ref "U$21") (pin "13") (pinfunction "OE_13") (pintype "bidirectional"))
      (node (ref "U$22") (pin "1") (pinfunction "GND_1") (pintype "bidirectional"))
      (node (ref "U$22") (pin "13") (pinfunction "OE_13") (pintype "bidirectional"))
      (node (ref "U$23") (pin "1") (pinfunction "GND_1") (pintype "bidirectional"))
      (node (ref "U$23") (pin "13") (pinfunction "OE_13") (pintype "bidirectional"))
      (node (ref "U$3") (pin "1") (pinfunction "GND_1") (pintype "power_in"))
      (node (ref "U$4") (pin "1") (pinfunction "GND_1") (pintype "power_in"))
      (node (ref "U$5") (pin "1") (pinfunction "GND_1") (pintype "power_in"))
      (node (ref "U$6") (pin "1") (pinfunction "GND_1") (pintype "power_in"))
      (node (ref "U$7") (pin "1") (pinfunction "GND_1") (pintype "power_in"))
      (node (ref "U$8") (pin "1") (pinfunction "GND_1") (pintype "power_in"))
      (node (ref "U$9") (pin "1") (pinfunction "GND_1") (pintype "power_in"))
      (node (ref "U1") (pin "GND@0") (pinfunction "GND_GND@0") (pintype "bidirectional"))
      (node (ref "U1") (pin "GND@1") (pinfunction "GND_GND@1") (pintype "bidirectional"))
      (node (ref "U1") (pin "GND@2") (pinfunction "GND_GND@2") (pintype "bidirectional"))
      (node (ref "U1") (pin "GND@3") (pinfunction "GND_GND@3") (pintype "bidirectional"))
      (node (ref "U1") (pin "GND@4") (pinfunction "GND_GND@4") (pintype "bidirectional"))
      (node (ref "X1") (pin "2") (pinfunction "S_2") (pintype "passive"))
      (node (ref "X1") (pin "3") (pinfunction "S_3") (pintype "passive"))
      (node (ref "X10") (pin "2") (pinfunction "S_2") (pintype "passive"))
      (node (ref "X10") (pin "3") (pinfunction "S_3") (pintype "passive"))
      (node (ref "X11") (pin "3") (pinfunction "S_3") (pintype "passive"))
      (node (ref "X11") (pin "4") (pinfunction "S_4") (pintype "passive"))
      (node (ref "X2") (pin "2") (pinfunction "S_2") (pintype "passive"))
      (node (ref "X2") (pin "3") (pinfunction "S_3") (pintype "passive"))
      (node (ref "X3") (pin "2") (pinfunction "S_2") (pintype "passive"))
      (node (ref "X3") (pin "3") (pinfunction "S_3") (pintype "passive"))
      (node (ref "X4") (pin "2") (pinfunction "S_2") (pintype "passive"))
      (node (ref "X4") (pin "3") (pinfunction "S_3") (pintype "passive"))
      (node (ref "X5") (pin "2") (pinfunction "S_2") (pintype "passive"))
      (node (ref "X5") (pin "3") (pinfunction "S_3") (pintype "passive"))
      (node (ref "X6") (pin "2") (pinfunction "S_2") (pintype "passive"))
      (node (ref "X6") (pin "3") (pinfunction "S_3") (pintype "passive"))
      (node (ref "X7") (pin "2") (pinfunction "S_2") (pintype "passive"))
      (node (ref "X7") (pin "3") (pinfunction "S_3") (pintype "passive"))
      (node (ref "X8") (pin "2") (pinfunction "S_2") (pintype "passive"))
      (node (ref "X8") (pin "3") (pinfunction "S_3") (pintype "passive"))
      (node (ref "X9") (pin "2") (pinfunction "S_2") (pintype "passive"))
      (node (ref "X9") (pin "3") (pinfunction "S_3") (pintype "passive"))
      (node (ref "XB1") (pin "10") (pinfunction "GND_10") (pintype "power_in"))
    )
    (net (code "45") (name "Net-(Q1-D)") (class "Default")
      (node (ref "Q1") (pin "3") (pinfunction "D_3") (pintype "passive"))
      (node (ref "R47") (pin "2") (pinfunction "2_2") (pintype "passive"))
      (node (ref "U1") (pin "18") (pinfunction "18(TX1)_18") (pintype "bidirectional"))
    )
    (net (code "46") (name "Net-(Q1-S)") (class "Default")
      (node (ref "Q1") (pin "2") (pinfunction "S_2") (pintype "passive"))
      (node (ref "R45") (pin "2") (pinfunction "2_2") (pintype "passive"))
      (node (ref "XB1") (pin "3") (pinfunction "DIN/~{CONFIG}_3") (pintype "input"))
    )
    (net (code "47") (name "Net-(Q2-D)") (class "Default")
      (node (ref "Q2") (pin "3") (pinfunction "D_3") (pintype "passive"))
      (node (ref "R48") (pin "2") (pinfunction "2_2") (pintype "passive"))
      (node (ref "U1") (pin "19") (pinfunction "19(RX1)_19") (pintype "bidirectional"))
    )
    (net (code "48") (name "Net-(Q2-S)") (class "Default")
      (node (ref "Q2") (pin "2") (pinfunction "S_2") (pintype "passive"))
      (node (ref "R46") (pin "2") (pinfunction "2_2") (pintype "passive"))
      (node (ref "XB1") (pin "2") (pinfunction "DOUT_2") (pintype "output"))
    )
    (net (code "49") (name "Net-(Q3-D)") (class "Default")
      (node (ref "Q3") (pin "3") (pinfunction "D_3") (pintype "passive"))
      (node (ref "R52") (pin "2") (pinfunction "2_2") (pintype "passive"))
      (node (ref "U1") (pin "16") (pinfunction "16(TX2)_16") (pintype "bidirectional"))
    )
    (net (code "50") (name "Net-(Q3-S)") (class "Default")
      (node (ref "JP1") (pin "2") (pinfunction "2_2") (pintype "passive"))
      (node (ref "Q3") (pin "2") (pinfunction "S_2") (pintype "passive"))
      (node (ref "R50") (pin "2") (pinfunction "2_2") (pintype "passive"))
    )
    (net (code "51") (name "Net-(Q4-D)") (class "Default")
      (node (ref "Q4") (pin "3") (pinfunction "D_3") (pintype "passive"))
      (node (ref "R53") (pin "2") (pinfunction "2_2") (pintype "passive"))
      (node (ref "U1") (pin "17") (pinfunction "17(RX2)_17") (pintype "bidirectional"))
    )
    (net (code "52") (name "Net-(Q4-S)") (class "Default")
      (node (ref "JP1") (pin "3") (pinfunction "3_3") (pintype "passive"))
      (node (ref "Q4") (pin "2") (pinfunction "S_2") (pintype "passive"))
      (node (ref "R51") (pin "2") (pinfunction "2_2") (pintype "passive"))
    )
    (net (code "53") (name "Net-(R41-Pad1)") (class "Default")
      (node (ref "R41") (pin "1") (pinfunction "1_1") (pintype "passive"))
      (node (ref "R43") (pin "2") (pinfunction "2_2") (pintype "passive"))
      (node (ref "U1") (pin "A15") (pinfunction "A15_A15") (pintype "bidirectional"))
    )
    (net (code "54") (name "Net-(R42-Pad2)") (class "Default")
      (node (ref "R42") (pin "2") (pinfunction "2_2") (pintype "passive"))
      (node (ref "R44") (pin "1") (pinfunction "1_1") (pintype "passive"))
      (node (ref "U1") (pin "A14") (pinfunction "A14_A14") (pintype "bidirectional"))
    )
    (net (code "55") (name "Net-(U$1-CS)") (class "Default")
      (node (ref "R1") (pin "2") (pinfunction "2_2") (pintype "passive"))
      (node (ref "R2") (pin "2") (pinfunction "2_2") (pintype "passive"))
      (node (ref "U$1") (pin "3") (pinfunction "CS_3") (pintype "bidirectional"))
    )
    (net (code "56") (name "Net-(U$2-CS)") (class "Default")
      (node (ref "R3") (pin "2") (pinfunction "2_2") (pintype "passive"))
      (node (ref "R4") (pin "2") (pinfunction "2_2") (pintype "passive"))
      (node (ref "U$2") (pin "3") (pinfunction "CS_3") (pintype "bidirectional"))
    )
    (net (code "57") (name "Net-(U$3-CS)") (class "Default")
      (node (ref "R5") (pin "2") (pinfunction "2_2") (pintype "passive"))
      (node (ref "R6") (pin "2") (pinfunction "2_2") (pintype "passive"))
      (node (ref "U$3") (pin "3") (pinfunction "CS_3") (pintype "bidirectional"))
    )
    (net (code "58") (name "Net-(U$4-CS)") (class "Default")
      (node (ref "R7") (pin "2") (pinfunction "2_2") (pintype "passive"))
      (node (ref "R8") (pin "2") (pinfunction "2_2") (pintype "passive"))
      (node (ref "U$4") (pin "3") (pinfunction "CS_3") (pintype "bidirectional"))
    )
    (net (code "59") (name "Net-(U$5-CS)") (class "Default")
      (node (ref "R10") (pin "2") (pinfunction "2_2") (pintype "passive"))
      (node (ref "R9") (pin "2") (pinfunction "2_2") (pintype "passive"))
      (node (ref "U$5") (pin "3") (pinfunction "CS_3") (pintype "bidirectional"))
    )
    (net (code "60") (name "Net-(U$6-CS)") (class "Default")
      (node (ref "R11") (pin "2") (pinfunction "2_2") (pintype "passive"))
      (node (ref "R12") (pin "2") (pinfunction "2_2") (pintype "passive"))
      (node (ref "U$6") (pin "3") (pinfunction "CS_3") (pintype "bidirectional"))
    )
    (net (code "61") (name "Net-(U$7-CS)") (class "Default")
      (node (ref "R13") (pin "2") (pinfunction "2_2") (pintype "passive"))
      (node (ref "R14") (pin "2") (pinfunction "2_2") (pintype "passive"))
      (node (ref "U$7") (pin "3") (pinfunction "CS_3") (pintype "bidirectional"))
    )
    (net (code "62") (name "Net-(U$8-CS)") (class "Default")
      (node (ref "R15") (pin "2") (pinfunction "2_2") (pintype "passive"))
      (node (ref "R16") (pin "2") (pinfunction "2_2") (pintype "passive"))
      (node (ref "U$8") (pin "3") (pinfunction "CS_3") (pintype "bidirectional"))
    )
    (net (code "63") (name "Net-(U$9-CS)") (class "Default")
      (node (ref "R17") (pin "2") (pinfunction "2_2") (pintype "passive"))
      (node (ref "R18") (pin "2") (pinfunction "2_2") (pintype "passive"))
      (node (ref "U$9") (pin "3") (pinfunction "CS_3") (pintype "bidirectional"))
    )
    (net (code "64") (name "Net-(U$10-CS)") (class "Default")
      (node (ref "R19") (pin "2") (pinfunction "2_2") (pintype "passive"))
      (node (ref "R20") (pin "2") (pinfunction "2_2") (pintype "passive"))
      (node (ref "U$10") (pin "3") (pinfunction "CS_3") (pintype "bidirectional"))
    )
    (net (code "65") (name "Net-(U$11-CS)") (class "Default")
      (node (ref "R21") (pin "2") (pinfunction "2_2") (pintype "passive"))
      (node (ref "R22") (pin "2") (pinfunction "2_2") (pintype "passive"))
      (node (ref "U$11") (pin "3") (pinfunction "CS_3") (pintype "bidirectional"))
    )
    (net (code "66") (name "Net-(U$12-CS)") (class "Default")
      (node (ref "R23") (pin "2") (pinfunction "2_2") (pintype "passive"))
      (node (ref "R24") (pin "2") (pinfunction "2_2") (pintype "passive"))
      (node (ref "U$12") (pin "3") (pinfunction "CS_3") (pintype "bidirectional"))
    )
    (net (code "67") (name "Net-(U$13-CS)") (class "Default")
      (node (ref "R25") (pin "2") (pinfunction "2_2") (pintype "passive"))
      (node (ref "R26") (pin "2") (pinfunction "2_2") (pintype "passive"))
      (node (ref "U$13") (pin "3") (pinfunction "CS_3") (pintype "bidirectional"))
    )
    (net (code "68") (name "Net-(U$14-CS)") (class "Default")
      (node (ref "R27") (pin "2") (pinfunction "2_2") (pintype "passive"))
      (node (ref "R28") (pin "2") (pinfunction "2_2") (pintype "passive"))
      (node (ref "U$14") (pin "3") (pinfunction "CS_3") (pintype "bidirectional"))
    )
    (net (code "69") (name "Net-(U$15-CS)") (class "Default")
      (node (ref "R29") (pin "2") (pinfunction "2_2") (pintype "passive"))
      (node (ref "R30") (pin "2") (pinfunction "2_2") (pintype "passive"))
      (node (ref "U$15") (pin "3") (pinfunction "CS_3") (pintype "bidirectional"))
    )
    (net (code "70") (name "Net-(U$16-CS)") (class "Default")
      (node (ref "R31") (pin "2") (pinfunction "2_2") (pintype "passive"))
      (node (ref "R32") (pin "2") (pinfunction "2_2") (pintype "passive"))
      (node (ref "U$16") (pin "3") (pinfunction "CS_3") (pintype "bidirectional"))
    )
    (net (code "71") (name "Net-(U$17-CS)") (class "Default")
      (node (ref "R33") (pin "2") (pinfunction "2_2") (pintype "passive"))
      (node (ref "R34") (pin "2") (pinfunction "2_2") (pintype "passive"))
      (node (ref "U$17") (pin "3") (pinfunction "CS_3") (pintype "bidirectional"))
    )
    (net (code "72") (name "Net-(U$18-CS)") (class "Default")
      (node (ref "R35") (pin "2") (pinfunction "2_2") (pintype "passive"))
      (node (ref "R36") (pin "2") (pinfunction "2_2") (pintype "passive"))
      (node (ref "U$18") (pin "3") (pinfunction "CS_3") (pintype "bidirectional"))
    )
    (net (code "73") (name "Net-(U$19-CS)") (class "Default")
      (node (ref "R37") (pin "2") (pinfunction "2_2") (pintype "passive"))
      (node (ref "R38") (pin "2") (pinfunction "2_2") (pintype "passive"))
      (node (ref "U$19") (pin "3") (pinfunction "CS_3") (pintype "bidirectional"))
    )
    (net (code "74") (name "Net-(U$20-CS)") (class "Default")
      (node (ref "R39") (pin "2") (pinfunction "2_2") (pintype "passive"))
      (node (ref "R40") (pin "2") (pinfunction "2_2") (pintype "passive"))
      (node (ref "U$20") (pin "3") (pinfunction "CS_3") (pintype "bidirectional"))
    )
    (net (code "75") (name "Net-(U$21-OUT0)") (class "Default")
      (node (ref "LED1") (pin "C") (pinfunction "C_C") (pintype "passive"))
      (node (ref "U$21") (pin "5") (pinfunction "OUT0_5") (pintype "bidirectional"))
    )
    (net (code "76") (name "Net-(U$21-OUT1)") (class "Default")
      (node (ref "LED2") (pin "C") (pinfunction "C_C") (pintype "passive"))
      (node (ref "U$21") (pin "6") (pinfunction "OUT1_6") (pintype "bidirectional"))
    )
    (net (code "77") (name "Net-(U$21-OUT2)") (class "Default")
      (node (ref "LED3") (pin "C") (pinfunction "C_C") (pintype "passive"))
      (node (ref "U$21") (pin "7") (pinfunction "OUT2_7") (pintype "bidirectional"))
    )
    (net (code "78") (name "Net-(U$21-OUT3)") (class "Default")
      (node (ref "LED4") (pin "C") (pinfunction "C_C") (pintype "passive"))
      (node (ref "U$21") (pin "8") (pinfunction "OUT3_8") (pintype "bidirectional"))
    )
    (net (code "79") (name "Net-(U$21-OUT4)") (class "Default")
      (node (ref "LED5") (pin "C") (pinfunction "C_C") (pintype "passive"))
      (node (ref "U$21") (pin "9") (pinfunction "OUT4_9") (pintype "bidirectional"))
    )
    (net (code "80") (name "Net-(U$21-OUT5)") (class "Default")
      (node (ref "LED6") (pin "C") (pinfunction "C_C") (pintype "passive"))
      (node (ref "U$21") (pin "10") (pinfunction "OUT5_10") (pintype "bidirectional"))
    )
    (net (code "81") (name "Net-(U$21-OUT6)") (class "Default")
      (node (ref "LED7") (pin "C") (pinfunction "C_C") (pintype "passive"))
      (node (ref "U$21") (pin "11") (pinfunction "OUT6_11") (pintype "bidirectional"))
    )
    (net (code "82") (name "Net-(U$21-OUT7)") (class "Default")
      (node (ref "LED8") (pin "C") (pinfunction "C_C") (pintype "passive"))
      (node (ref "U$21") (pin "12") (pinfunction "OUT7_12") (pintype "bidirectional"))
    )
    (net (code "83") (name "Net-(U$21-REXT)") (class "Default")
      (node (ref "R67") (pin "2") (pinfunction "2_2") (pintype "passive"))
      (node (ref "U$21") (pin "15") (pinfunction "REXT_15") (pintype "bidirectional"))
    )
    (net (code "84") (name "Net-(U$21-SDO)") (class "Default")
      (node (ref "U$21") (pin "14") (pinfunction "SDO_14") (pintype "bidirectional"))
      (node (ref "U$22") (pin "2") (pinfunction "SDI_2") (pintype "bidirectional"))
    )
    (net (code "85") (name "Net-(U$22-OUT0)") (class "Default")
      (node (ref "LED9") (pin "C") (pinfunction "C_C") (pintype "passive"))
      (node (ref "U$22") (pin "5") (pinfunction "OUT0_5") (pintype "bidirectional"))
    )
    (net (code "86") (name "Net-(U$22-OUT1)") (class "Default")
      (node (ref "LED10") (pin "C") (pinfunction "C_C") (pintype "passive"))
      (node (ref "U$22") (pin "6") (pinfunction "OUT1_6") (pintype "bidirectional"))
    )
    (net (code "87") (name "Net-(U$22-OUT2)") (class "Default")
      (node (ref "LED11") (pin "C") (pinfunction "C_C") (pintype "passive"))
      (node (ref "U$22") (pin "7") (pinfunction "OUT2_7") (pintype "bidirectional"))
    )
    (net (code "88") (name "Net-(U$22-OUT3)") (class "Default")
      (node (ref "LED12") (pin "C") (pinfunction "C_C") (pintype "passive"))
      (node (ref "U$22") (pin "8") (pinfunction "OUT3_8") (pintype "bidirectional"))
    )
    (net (code "89") (name "Net-(U$22-OUT4)") (class "Default")
      (node (ref "LED13") (pin "C") (pinfunction "C_C") (pintype "passive"))
      (node (ref "U$22") (pin "9") (pinfunction "OUT4_9") (pintype "bidirectional"))
    )
    (net (code "90") (name "Net-(U$22-OUT5)") (class "Default")
      (node (ref "LED14") (pin "C") (pinfunction "C_C") (pintype "passive"))
      (node (ref "U$22") (pin "10") (pinfunction "OUT5_10") (pintype "bidirectional"))
    )
    (net (code "91") (name "Net-(U$22-OUT6)") (class "Default")
      (node (ref "LED15") (pin "C") (pinfunction "C_C") (pintype "passive"))
      (node (ref "U$22") (pin "11") (pinfunction "OUT6_11") (pintype "bidirectional"))
    )
    (net (code "92") (name "Net-(U$22-OUT7)") (class "Default")
      (node (ref "LED16") (pin "C") (pinfunction "C_C") (pintype "passive"))
      (node (ref "U$22") (pin "12") (pinfunction "OUT7_12") (pintype "bidirectional"))
    )
    (net (code "93") (name "Net-(U$22-REXT)") (class "Default")
      (node (ref "R65") (pin "2") (pinfunction "2_2") (pintype "passive"))
      (node (ref "U$22") (pin "15") (pinfunction "REXT_15") (pintype "bidirectional"))
    )
    (net (code "94") (name "Net-(U$22-SDO)") (class "Default")
      (node (ref "U$22") (pin "14") (pinfunction "SDO_14") (pintype "bidirectional"))
      (node (ref "U$23") (pin "2") (pinfunction "SDI_2") (pintype "bidirectional"))
    )
    (net (code "95") (name "Net-(U$23-OUT0)") (class "Default")
      (node (ref "LED17") (pin "C") (pinfunction "C_C") (pintype "passive"))
      (node (ref "U$23") (pin "5") (pinfunction "OUT0_5") (pintype "bidirectional"))
    )
    (net (code "96") (name "Net-(U$23-OUT1)") (class "Default")
      (node (ref "LED18") (pin "C") (pinfunction "C_C") (pintype "passive"))
      (node (ref "U$23") (pin "6") (pinfunction "OUT1_6") (pintype "bidirectional"))
    )
    (net (code "97") (name "Net-(U$23-OUT2)") (class "Default")
      (node (ref "LED19") (pin "C") (pinfunction "C_C") (pintype "passive"))
      (node (ref "U$23") (pin "7") (pinfunction "OUT2_7") (pintype "bidirectional"))
    )
    (net (code "98") (name "Net-(U$23-OUT3)") (class "Default")
      (node (ref "LED20") (pin "C") (pinfunction "C_C") (pintype "passive"))
      (node (ref "U$23") (pin "8") (pinfunction "OUT3_8") (pintype "bidirectional"))
    )
    (net (code "99") (name "Net-(U$23-OUT4)") (class "Default")
      (node (ref "LED21") (pin "C") (pinfunction "C_C") (pintype "passive"))
      (node (ref "U$23") (pin "9") (pinfunction "OUT4_9") (pintype "bidirectional"))
    )
    (net (code "100") (name "Net-(U$23-OUT5)") (class "Default")
      (node (ref "LED22") (pin "C") (pinfunction "C_C") (pintype "passive"))
      (node (ref "U$23") (pin "10") (pinfunction "OUT5_10") (pintype "bidirectional"))
    )
    (net (code "101") (name "Net-(U$23-OUT6)") (class "Default")
      (node (ref "LED23") (pin "C") (pinfunction "C_C") (pintype "passive"))
      (node (ref "U$23") (pin "11") (pinfunction "OUT6_11") (pintype "bidirectional"))
    )
    (net (code "102") (name "Net-(U$23-OUT7)") (class "Default")
      (node (ref "LED24") (pin "C") (pinfunction "C_C") (pintype "passive"))
      (node (ref "U$23") (pin "12") (pinfunction "OUT7_12") (pintype "bidirectional"))
    )
    (net (code "103") (name "Net-(U$23-REXT)") (class "Default")
      (node (ref "R49") (pin "2") (pinfunction "2_2") (pintype "passive"))
      (node (ref "U$23") (pin "15") (pinfunction "REXT_15") (pintype "bidirectional"))
    )
    (net (code "104") (name "Net-(X1A-S)") (class "Default")
      (node (ref "U$1") (pin "6") (pinfunction "OUT_6") (pintype "output"))
      (node (ref "U$1") (pin "7") (pinfunction "OUT_7") (pintype "output"))
      (node (ref "X1") (pin "1") (pinfunction "S_1") (pintype "passive"))
    )
    (net (code "105") (name "Net-(X1D-S)") (class "Default")
      (node (ref "U$2") (pin "6") (pinfunction "OUT_6") (pintype "output"))
      (node (ref "U$2") (pin "7") (pinfunction "OUT_7") (pintype "output"))
      (node (ref "X1") (pin "4") (pinfunction "S_4") (pintype "passive"))
    )
    (net (code "106") (name "Net-(X2A-S)") (class "Default")
      (node (ref "U$3") (pin "6") (pinfunction "OUT_6") (pintype "output"))
      (node (ref "U$3") (pin "7") (pinfunction "OUT_7") (pintype "output"))
      (node (ref "X2") (pin "1") (pinfunction "S_1") (pintype "passive"))
    )
    (net (code "107") (name "Net-(X2D-S)") (class "Default")
      (node (ref "U$4") (pin "6") (pinfunction "OUT_6") (pintype "output"))
      (node (ref "U$4") (pin "7") (pinfunction "OUT_7") (pintype "output"))
      (node (ref "X2") (pin "4") (pinfunction "S_4") (pintype "passive"))
    )
    (net (code "108") (name "Net-(X3A-S)") (class "Default")
      (node (ref "U$5") (pin "6") (pinfunction "OUT_6") (pintype "output"))
      (node (ref "U$5") (pin "7") (pinfunction "OUT_7") (pintype "output"))
      (node (ref "X3") (pin "1") (pinfunction "S_1") (pintype "passive"))
    )
    (net (code "109") (name "Net-(X3D-S)") (class "Default")
      (node (ref "U$6") (pin "6") (pinfunction "OUT_6") (pintype "output"))
      (node (ref "U$6") (pin "7") (pinfunction "OUT_7") (pintype "output"))
      (node (ref "X3") (pin "4") (pinfunction "S_4") (pintype "passive"))
    )
    (net (code "110") (name "Net-(X4A-S)") (class "Default")
      (node (ref "U$7") (pin "6") (pinfunction "OUT_6") (pintype "output"))
      (node (ref "U$7") (pin "7") (pinfunction "OUT_7") (pintype "output"))
      (node (ref "X4") (pin "1") (pinfunction "S_1") (pintype "passive"))
    )
    (net (code "111") (name "Net-(X4D-S)") (class "Default")
      (node (ref "U$8") (pin "6") (pinfunction "OUT_6") (pintype "output"))
      (node (ref "U$8") (pin "7") (pinfunction "OUT_7") (pintype "output"))
      (node (ref "X4") (pin "4") (pinfunction "S_4") (pintype "passive"))
    )
    (net (code "112") (name "Net-(X5A-S)") (class "Default")
      (node (ref "U$9") (pin "6") (pinfunction "OUT_6") (pintype "output"))
      (node (ref "U$9") (pin "7") (pinfunction "OUT_7") (pintype "output"))
      (node (ref "X5") (pin "1") (pinfunction "S_1") (pintype "passive"))
    )
    (net (code "113") (name "Net-(X5D-S)") (class "Default")
      (node (ref "U$10") (pin "6") (pinfunction "OUT_6") (pintype "output"))
      (node (ref "U$10") (pin "7") (pinfunction "OUT_7") (pintype "output"))
      (node (ref "X5") (pin "4") (pinfunction "S_4") (pintype "passive"))
    )
    (net (code "114") (name "Net-(X6A-S)") (class "Default")
      (node (ref "U$11") (pin "6") (pinfunction "OUT_6") (pintype "output"))
      (node (ref "U$11") (pin "7") (pinfunction "OUT_7") (pintype "output"))
      (node (ref "X6") (pin "1") (pinfunction "S_1") (pintype "passive"))
    )
    (net (code "115") (name "Net-(X6D-S)") (class "Default")
      (node (ref "U$12") (pin "6") (pinfunction "OUT_6") (pintype "output"))
      (node (ref "U$12") (pin "7") (pinfunction "OUT_7") (pintype "output"))
      (node (ref "X6") (pin "4") (pinfunction "S_4") (pintype "passive"))
    )
    (net (code "116") (name "Net-(X7A-S)") (class "Default")
      (node (ref "U$13") (pin "6") (pinfunction "OUT_6") (pintype "output"))
      (node (ref "U$13") (pin "7") (pinfunction "OUT_7") (pintype "output"))
      (node (ref "X7") (pin "1") (pinfunction "S_1") (pintype "passive"))
    )
    (net (code "117") (name "Net-(X7D-S)") (class "Default")
      (node (ref "U$14") (pin "6") (pinfunction "OUT_6") (pintype "output"))
      (node (ref "U$14") (pin "7") (pinfunction "OUT_7") (pintype "output"))
      (node (ref "X7") (pin "4") (pinfunction "S_4") (pintype "passive"))
    )
    (net (code "118") (name "Net-(X8A-S)") (class "Default")
      (node (ref "U$15") (pin "6") (pinfunction "OUT_6") (pintype "output"))
      (node (ref "U$15") (pin "7") (pinfunction "OUT_7") (pintype "output"))
      (node (ref "X8") (pin "1") (pinfunction "S_1") (pintype "passive"))
    )
    (net (code "119") (name "Net-(X8D-S)") (class "Default")
      (node (ref "U$16") (pin "6") (pinfunction "OUT_6") (pintype "output"))
      (node (ref "U$16") (pin "7") (pinfunction "OUT_7") (pintype "output"))
      (node (ref "X8") (pin "4") (pinfunction "S_4") (pintype "passive"))
    )
    (net (code "120") (name "Net-(X9A-S)") (class "Default")
      (node (ref "U$17") (pin "6") (pinfunction "OUT_6") (pintype "output"))
      (node (ref "U$17") (pin "7") (pinfunction "OUT_7") (pintype "output"))
      (node (ref "X9") (pin "1") (pinfunction "S_1") (pintype "passive"))
    )
    (net (code "121") (name "Net-(X9D-S)") (class "Default")
      (node (ref "U$18") (pin "6") (pinfunction "OUT_6") (pintype "output"))
      (node (ref "U$18") (pin "7") (pinfunction "OUT_7") (pintype "output"))
      (node (ref "X9") (pin "4") (pinfunction "S_4") (pintype "passive"))
    )
    (net (code "122") (name "Net-(X10A-S)") (class "Default")
      (node (ref "U$19") (pin "6") (pinfunction "OUT_6") (pintype "output"))
      (node (ref "U$19") (pin "7") (pinfunction "OUT_7") (pintype "output"))
      (node (ref "X10") (pin "1") (pinfunction "S_1") (pintype "passive"))
    )
    (net (code "123") (name "Net-(X10D-S)") (class "Default")
      (node (ref "U$20") (pin "6") (pinfunction "OUT_6") (pintype "output"))
      (node (ref "U$20") (pin "7") (pinfunction "OUT_7") (pintype "output"))
      (node (ref "X10") (pin "4") (pinfunction "S_4") (pintype "passive"))
    )
    (net (code "124") (name "VCC") (class "Default")
      (node (ref "C4") (pin "+") (pinfunction "+_+") (pintype "passive"))
      (node (ref "R47") (pin "1") (pinfunction "1_1") (pintype "passive"))
      (node (ref "R48") (pin "1") (pinfunction "1_1") (pintype "passive"))
      (node (ref "R52") (pin "1") (pinfunction "1_1") (pintype "passive"))
      (node (ref "R53") (pin "1") (pinfunction "1_1") (pintype "passive"))
      (node (ref "U$21") (pin "16") (pinfunction "VDD_16") (pintype "bidirectional"))
      (node (ref "U$22") (pin "16") (pinfunction "VDD_16") (pintype "bidirectional"))
      (node (ref "U$23") (pin "16") (pinfunction "VDD_16") (pintype "bidirectional"))
      (node (ref "U1") (pin "5V@0") (pinfunction "5V_5V@0") (pintype "bidirectional"))
      (node (ref "U1") (pin "5V@1") (pinfunction "5V_5V@1") (pintype "bidirectional"))
      (node (ref "U1") (pin "5V@2") (pinfunction "5V_5V@2") (pintype "bidirectional"))
    )
    (net (code "125") (name "VDD") (class "Default")
      (node (ref "C2") (pin "+") (pinfunction "+_+") (pintype "passive"))
      (node (ref "C3") (pin "+") (pinfunction "+_+") (pintype "passive"))
      (node (ref "R43") (pin "1") (pinfunction "1_1") (pintype "passive"))
      (node (ref "S1") (pin "P$3") (pinfunction "S_P$3") (pintype "passive"))
      (node (ref "U$1") (pin "5") (pinfunction "VCC_5") (pintype "power_in"))
      (node (ref "U$1") (pin "8") (pinfunction "VCC_8") (pintype "power_in"))
      (node (ref "U$10") (pin "5") (pinfunction "VCC_5") (pintype "power_in"))
      (node (ref "U$10") (pin "8") (pinfunction "VCC_8") (pintype "power_in"))
      (node (ref "U$11") (pin "5") (pinfunction "VCC_5") (pintype "power_in"))
      (node (ref "U$11") (pin "8") (pinfunction "VCC_8") (pintype "power_in"))
      (node (ref "U$12") (pin "5") (pinfunction "VCC_5") (pintype "power_in"))
      (node (ref "U$12") (pin "8") (pinfunction "VCC_8") (pintype "power_in"))
      (node (ref "U$13") (pin "5") (pinfunction "VCC_5") (pintype "power_in"))
      (node (ref "U$13") (pin "8") (pinfunction "VCC_8") (pintype "power_in"))
      (node (ref "U$14") (pin "5") (pinfunction "VCC_5") (pintype "power_in"))
      (node (ref "U$14") (pin "8") (pinfunction "VCC_8") (pintype "power_in"))
      (node (ref "U$15") (pin "5") (pinfunction "VCC_5") (pintype "power_in"))
      (node (ref "U$15") (pin "8") (pinfunction "VCC_8") (pintype "power_in"))
      (node (ref "U$16") (pin "5") (pinfunction "VCC_5") (pintype "power_in"))
      (node (ref "U$16") (pin "8") (pinfunction "VCC_8") (pintype "power_in"))
      (node (ref "U$17") (pin "5") (pinfunction "VCC_5") (pintype "power_in"))
      (node (ref "U$17") (pin "8") (pinfunction "VCC_8") (pintype "power_in"))
      (node (ref "U$18") (pin "5") (pinfunction "VCC_5") (pintype "power_in"))
      (node (ref "U$18") (pin "8") (pinfunction "VCC_8") (pintype "power_in"))
      (node (ref "U$19") (pin "5") (pinfunction "VCC_5") (pintype "power_in"))
      (node (ref "U$19") (pin "8") (pinfunction "VCC_8") (pintype "power_in"))
      (node (ref "U$2") (pin "5") (pinfunction "VCC_5") (pintype "power_in"))
      (node (ref "U$2") (pin "8") (pinfunction "VCC_8") (pintype "power_in"))
      (node (ref "U$20") (pin "5") (pinfunction "VCC_5") (pintype "power_in"))
      (node (ref "U$20") (pin "8") (pinfunction "VCC_8") (pintype "power_in"))
      (node (ref "U$3") (pin "5") (pinfunction "VCC_5") (pintype "power_in"))
      (node (ref "U$3") (pin "8") (pinfunction "VCC_8") (pintype "power_in"))
      (node (ref "U$4") (pin "5") (pinfunction "VCC_5") (pintype "power_in"))
      (node (ref "U$4") (pin "8") (pinfunction "VCC_8") (pintype "power_in"))
      (node (ref "U$5") (pin "5") (pinfunction "VCC_5") (pintype "power_in"))
      (node (ref "U$5") (pin "8") (pinfunction "VCC_8") (pintype "power_in"))
      (node (ref "U$6") (pin "5") (pinfunction "VCC_5") (pintype "power_in"))
      (node (ref "U$6") (pin "8") (pinfunction "VCC_8") (pintype "power_in"))
      (node (ref "U$7") (pin "5") (pinfunction "VCC_5") (pintype "power_in"))
      (node (ref "U$7") (pin "8") (pinfunction "VCC_8") (pintype "power_in"))
      (node (ref "U$8") (pin "5") (pinfunction "VCC_5") (pintype "power_in"))
      (node (ref "U$8") (pin "8") (pinfunction "VCC_8") (pintype "power_in"))
      (node (ref "U$9") (pin "5") (pinfunction "VCC_5") (pintype "power_in"))
      (node (ref "U$9") (pin "8") (pinfunction "VCC_8") (pintype "power_in"))
    )
    (net (code "126") (name "unconnected-(JP1-Pad1)") (class "Default")
      (node (ref "JP1") (pin "1") (pinfunction "1_1") (pintype "passive"))
    )
    (net (code "127") (name "unconnected-(JP1-Pad4)") (class "Default")
      (node (ref "JP1") (pin "4") (pinfunction "4_4") (pintype "passive"))
    )
    (net (code "128") (name "unconnected-(Q2-G-Pad1)") (class "Default")
      (node (ref "Q2") (pin "1") (pinfunction "G_1") (pintype "passive"))
    )
    (net (code "129") (name "unconnected-(Q4-G-Pad1)") (class "Default")
      (node (ref "Q4") (pin "1") (pinfunction "G_1") (pintype "passive"))
    )
    (net (code "130") (name "unconnected-(S1-O-PadP$1)") (class "Default")
      (node (ref "S1") (pin "P$1") (pinfunction "O_P$1") (pintype "passive"))
    )
    (net (code "131") (name "unconnected-(U$23-SDO-Pad14)") (class "Default")
      (node (ref "U$23") (pin "14") (pinfunction "SDO_14") (pintype "bidirectional"))
    )
    (net (code "132") (name "unconnected-(U1-0(RX0)-Pad0)") (class "Default")
      (node (ref "U1") (pin "0") (pinfunction "0(RX0)_0") (pintype "bidirectional"))
    )
    (net (code "133") (name "unconnected-(U1-1(TX0)-Pad1)") (class "Default")
      (node (ref "U1") (pin "1") (pinfunction "1(TX0)_1") (pintype "bidirectional"))
    )
    (net (code "134") (name "unconnected-(U1-14(TX3)-Pad14)") (class "Default")
      (node (ref "U1") (pin "14") (pinfunction "14(TX3)_14") (pintype "bidirectional"))
    )
    (net (code "135") (name "unconnected-(U1-15(RX3)-Pad15)") (class "Default")
      (node (ref "U1") (pin "15") (pinfunction "15(RX3)_15") (pintype "bidirectional"))
    )
    (net (code "136") (name "unconnected-(U1-20(SDA)-Pad20)") (class "Default")
      (node (ref "U1") (pin "20") (pinfunction "20(SDA)_20") (pintype "bidirectional"))
    )
    (net (code "137") (name "unconnected-(U1-21(SCL)-Pad21)") (class "Default")
      (node (ref "U1") (pin "21") (pinfunction "21(SCL)_21") (pintype "bidirectional"))
    )
    (net (code "138") (name "unconnected-(U1-Pad2)") (class "Default")
      (node (ref "U1") (pin "2") (pinfunction "2_2") (pintype "bidirectional"))
    )
    (net (code "139") (name "unconnected-(U1-Pad3)") (class "Default")
      (node (ref "U1") (pin "3") (pinfunction "3_3") (pintype "bidirectional"))
    )
    (net (code "140") (name "unconnected-(U1-Pad7)") (class "Default")
      (node (ref "U1") (pin "7") (pinfunction "7_7") (pintype "bidirectional"))
    )
    (net (code "141") (name "unconnected-(U1-Pad8)") (class "Default")
      (node (ref "U1") (pin "8") (pinfunction "8_8") (pintype "bidirectional"))
    )
    (net (code "142") (name "unconnected-(U1-Pad9)") (class "Default")
      (node (ref "U1") (pin "9") (pinfunction "9_9") (pintype "bidirectional"))
    )
    (net (code "143") (name "unconnected-(U1-Pad12)") (class "Default")
      (node (ref "U1") (pin "12") (pinfunction "12_12") (pintype "bidirectional"))
    )
    (net (code "144") (name "unconnected-(U1-Pad13)") (class "Default")
      (node (ref "U1") (pin "13") (pinfunction "13_13") (pintype "bidirectional"))
    )
    (net (code "145") (name "unconnected-(U1-Pad47)") (class "Default")
      (node (ref "U1") (pin "47") (pinfunction "47_47") (pintype "bidirectional"))
    )
    (net (code "146") (name "unconnected-(U1-Pad48)") (class "Default")
      (node (ref "U1") (pin "48") (pinfunction "48_48") (pintype "bidirectional"))
    )
    (net (code "147") (name "unconnected-(U1-Pad49)") (class "Default")
      (node (ref "U1") (pin "49") (pinfunction "49_49") (pintype "bidirectional"))
    )
    (net (code "148") (name "unconnected-(U1-Pad50)") (class "Default")
      (node (ref "U1") (pin "50") (pinfunction "50_50") (pintype "bidirectional"))
    )
    (net (code "149") (name "unconnected-(U1-Pad51)") (class "Default")
      (node (ref "U1") (pin "51") (pinfunction "51_51") (pintype "bidirectional"))
    )
    (net (code "150") (name "unconnected-(U1-Pad52)") (class "Default")
      (node (ref "U1") (pin "52") (pinfunction "52_52") (pintype "bidirectional"))
    )
    (net (code "151") (name "unconnected-(U1-PadA10)") (class "Default")
      (node (ref "U1") (pin "A10") (pinfunction "A10_A10") (pintype "bidirectional"))
    )
    (net (code "152") (name "unconnected-(U1-PadA11)") (class "Default")
      (node (ref "U1") (pin "A11") (pinfunction "A11_A11") (pintype "bidirectional"))
    )
    (net (code "153") (name "unconnected-(U1-PadA12)") (class "Default")
      (node (ref "U1") (pin "A12") (pinfunction "A12_A12") (pintype "bidirectional"))
    )
    (net (code "154") (name "unconnected-(U1-PadA13)") (class "Default")
      (node (ref "U1") (pin "A13") (pinfunction "A13_A13") (pintype "bidirectional"))
    )
    (net (code "155") (name "unconnected-(U1-PadAREF)") (class "Default")
      (node (ref "U1") (pin "AREF") (pinfunction "AREF_AREF") (pintype "bidirectional"))
    )
    (net (code "156") (name "unconnected-(U1-PadRESET)") (class "Default")
      (node (ref "U1") (pin "RESET") (pinfunction "RESET_RESET") (pintype "bidirectional"))
    )
    (net (code "157") (name "unconnected-(XB1-AD0{slash}DIO0-Pad20)") (class "Default")
      (node (ref "XB1") (pin "20") (pinfunction "AD0/DIO0_20") (pintype "bidirectional"))
    )
    (net (code "158") (name "unconnected-(XB1-AD1{slash}DIO1-Pad19)") (class "Default")
      (node (ref "XB1") (pin "19") (pinfunction "AD1/DIO1_19") (pintype "bidirectional"))
    )
    (net (code "159") (name "unconnected-(XB1-AD2{slash}DIO2-Pad18)") (class "Default")
      (node (ref "XB1") (pin "18") (pinfunction "AD2/DIO2_18") (pintype "bidirectional"))
    )
    (net (code "160") (name "unconnected-(XB1-ASSOC{slash}AD5{slash}DIO5-Pad15)") (class "Default")
      (node (ref "XB1") (pin "15") (pinfunction "ASSOC/AD5/DIO5_15") (pintype "bidirectional"))
    )
    (net (code "161") (name "unconnected-(XB1-CD{slash}DOUT_EN{slash}DO8-Pad4)") (class "Default")
      (node (ref "XB1") (pin "4") (pinfunction "CD/DOUT_EN/DO8_4") (pintype "output"))
    )
    (net (code "162") (name "unconnected-(XB1-COORD_SEL{slash}AD3{slash}DIO3-Pad17)") (class "Default")
      (node (ref "XB1") (pin "17") (pinfunction "COORD_SEL/AD3/DIO3_17") (pintype "bidirectional"))
    )
    (net (code "163") (name "unconnected-(XB1-ON{slash}~{SLEEP}-Pad13)") (class "Default")
      (node (ref "XB1") (pin "13") (pinfunction "ON/~{SLEEP}_13") (pintype "output"))
    )
    (net (code "164") (name "unconnected-(XB1-PWM0{slash}RSSI-Pad6)") (class "Default")
      (node (ref "XB1") (pin "6") (pinfunction "PWM0/RSSI_6") (pintype "output"))
    )
    (net (code "165") (name "unconnected-(XB1-RF_TX{slash}AD4{slash}DIO4-Pad11)") (class "Default")
      (node (ref "XB1") (pin "11") (pinfunction "RF_TX/AD4/DIO4_11") (pintype "bidirectional"))
    )
    (net (code "166") (name "unconnected-(XB1-VREF-Pad14)") (class "Default")
      (node (ref "XB1") (pin "14") (pinfunction "VREF_14") (pintype "input"))
    )
    (net (code "167") (name "unconnected-(XB1-~{CTS}{slash}DIO7-Pad12)") (class "Default")
      (node (ref "XB1") (pin "12") (pinfunction "~{CTS}/DIO7_12") (pintype "bidirectional"))
    )
    (net (code "168") (name "unconnected-(XB1-~{DTR}{slash}SLEEP_RQ{slash}DI8-Pad9)") (class "Default")
      (node (ref "XB1") (pin "9") (pinfunction "~{DTR}/SLEEP_RQ/DI8_9") (pintype "bidirectional"))
    )
    (net (code "169") (name "unconnected-(XB1-~{RTS}{slash}AD6{slash}DIO6-Pad16)") (class "Default")
      (node (ref "XB1") (pin "16") (pinfunction "~{RTS}/AD6/DIO6_16") (pintype "bidirectional"))
    )
  )
)
